# Motors_Sheet.net
KiCad netlist of a schematic drawn in Altium Designer
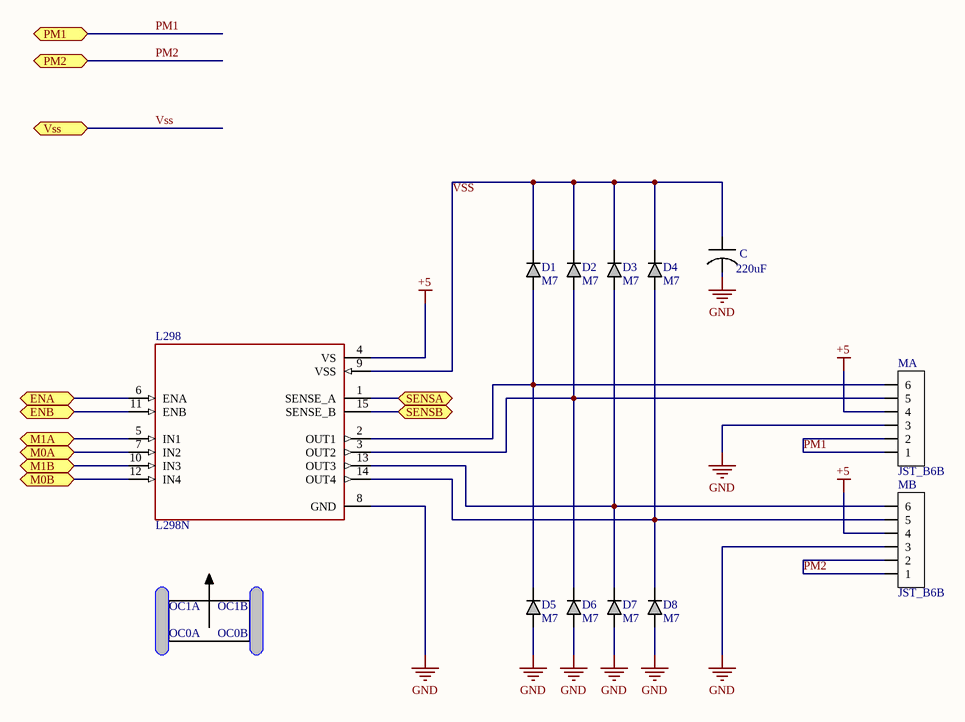
[diagram p0: Motors_Sheet.SchDoc]

(export (version "E")
  (design (tool "Eeschema 10.0.6"))
  (components
    (comp (ref "C")
      (value "220uF")
      (footprint "CAP_8115")
      (fields (field (name "Comment") "cap_elec8115"))
      (libsource (lib "cap_elec") (part "cap_elec8115"))
    )
    (comp (ref "D1") (value "M7") (footprint "1N4007") (libsource (lib "1N4007") (part "1N4007")))
    (comp (ref "D2") (value "M7") (footprint "1N4007") (libsource (lib "1N4007") (part "1N4007")))
    (comp (ref "D3") (value "M7") (footprint "1N4007") (libsource (lib "1N4007") (part "1N4007")))
    (comp (ref "D4") (value "M7") (footprint "1N4007") (libsource (lib "1N4007") (part "1N4007")))
    (comp (ref "D5") (value "M7") (footprint "1N4007") (libsource (lib "1N4007") (part "1N4007")))
    (comp (ref "D6") (value "M7") (footprint "1N4007") (libsource (lib "1N4007") (part "1N4007")))
    (comp (ref "D7") (value "M7") (footprint "1N4007") (libsource (lib "1N4007") (part "1N4007")))
    (comp (ref "D8") (value "M7") (footprint "1N4007") (libsource (lib "1N4007") (part "1N4007")))
    (comp (ref "L298") (value "L298N") (footprint "L298N") (libsource (lib "L298N") (part "L298N")))
    (comp (ref "MA") (value "JST_B6B") (footprint "JST_B6B") (libsource (lib "JST_B6B") (part "JST_B6B")))
    (comp (ref "MB") (value "JST_B6B") (footprint "JST_B6B") (libsource (lib "JST_B6B") (part "JST_B6B")))
  )
  (nets
    (net (code "1") (name "+5") (class "Default")
      (node (ref "L298") (pin "4") (pinfunction "VS_4") (pintype "power_in"))
      (node (ref "MA") (pin "4") (pinfunction "4_4") (pintype "passive"))
      (node (ref "MB") (pin "4") (pinfunction "4_4") (pintype "passive"))
    )
    (net (code "2") (name "/ENA") (class "Default")
      (node (ref "L298") (pin "6") (pinfunction "ENA_6") (pintype "input"))
    )
    (net (code "3") (name "/ENB") (class "Default")
      (node (ref "L298") (pin "11") (pinfunction "ENB_11") (pintype "input"))
    )
    (net (code "4") (name "/M0A") (class "Default")
      (node (ref "L298") (pin "7") (pinfunction "IN2_7") (pintype "input"))
    )
    (net (code "5") (name "/M0B") (class "Default")
      (node (ref "L298") (pin "12") (pinfunction "IN4_12") (pintype "input"))
    )
    (net (code "6") (name "/M1A") (class "Default")
      (node (ref "L298") (pin "5") (pinfunction "IN1_5") (pintype "input"))
    )
    (net (code "7") (name "/M1B") (class "Default")
      (node (ref "L298") (pin "10") (pinfunction "IN3_10") (pintype "input"))
    )
    (net (code "8") (name "/PM1") (class "Default")
      (node (ref "MA") (pin "1") (pinfunction "1_1") (pintype "passive"))
      (node (ref "MA") (pin "2") (pinfunction "2_2") (pintype "passive"))
    )
    (net (code "9") (name "/PM2") (class "Default")
      (node (ref "MB") (pin "1") (pinfunction "1_1") (pintype "passive"))
      (node (ref "MB") (pin "2") (pinfunction "2_2") (pintype "passive"))
    )
    (net (code "10") (name "/SENSA") (class "Default")
      (node (ref "L298") (pin "1") (pinfunction "SENSE_A_1") (pintype "passive"))
    )
    (net (code "11") (name "/SENSB") (class "Default")
      (node (ref "L298") (pin "15") (pinfunction "SENSE_B_15") (pintype "passive"))
    )
    (net (code "12") (name "/VSS") (class "Default")
      (node (ref "C") (pin "pos") (pinfunction "pos_pos") (pintype "passive"))
      (node (ref "D1") (pin "C") (pinfunction "C_C") (pintype "passive"))
      (node (ref "D2") (pin "C") (pinfunction "C_C") (pintype "passive"))
      (node (ref "D3") (pin "C") (pinfunction "C_C") (pintype "passive"))
      (node (ref "D4") (pin "C") (pinfunction "C_C") (pintype "passive"))
      (node (ref "L298") (pin "9") (pinfunction "VSS_9") (pintype "input"))
    )
    (net (code "14") (name "GND") (class "Default")
      (node (ref "C") (pin "neg") (pinfunction "neg_neg") (pintype "passive"))
      (node (ref "D5") (pin "A") (pinfunction "A_A") (pintype "passive"))
      (node (ref "D6") (pin "A") (pinfunction "A_A") (pintype "passive"))
      (node (ref "D7") (pin "A") (pinfunction "A_A") (pintype "passive"))
      (node (ref "D8") (pin "A") (pinfunction "A_A") (pintype "passive"))
      (node (ref "L298") (pin "8") (pinfunction "GND_8") (pintype "power_in"))
      (node (ref "MA") (pin "3") (pinfunction "3_3") (pintype "passive"))
      (node (ref "MB") (pin "3") (pinfunction "3_3") (pintype "passive"))
    )
    (net (code "15") (name "Net-(L298-OUT1)") (class "Default")
      (node (ref "D1") (pin "A") (pinfunction "A_A") (pintype "passive"))
      (node (ref "D5") (pin "C") (pinfunction "C_C") (pintype "passive"))
      (node (ref "L298") (pin "2") (pinfunction "OUT1_2") (pintype "output"))
      (node (ref "MA") (pin "6") (pinfunction "6_6") (pintype "passive"))
    )
    (net (code "16") (name "Net-(L298-OUT2)") (class "Default")
      (node (ref "D2") (pin "A") (pinfunction "A_A") (pintype "passive"))
      (node (ref "D6") (pin "C") (pinfunction "C_C") (pintype "passive"))
      (node (ref "L298") (pin "3") (pinfunction "OUT2_3") (pintype "output"))
      (node (ref "MA") (pin "5") (pinfunction "5_5") (pintype "passive"))
    )
    (net (code "17") (name "Net-(L298-OUT3)") (class "Default")
      (node (ref "D3") (pin "A") (pinfunction "A_A") (pintype "passive"))
      (node (ref "D7") (pin "C") (pinfunction "C_C") (pintype "passive"))
      (node (ref "L298") (pin "13") (pinfunction "OUT3_13") (pintype "output"))
      (node (ref "MB") (pin "6") (pinfunction "6_6") (pintype "passive"))
    )
    (net (code "18") (name "Net-(L298-OUT4)") (class "Default")
      (node (ref "D4") (pin "A") (pinfunction "A_A") (pintype "passive"))
      (node (ref "D8") (pin "C") (pinfunction "C_C") (pintype "passive"))
      (node (ref "L298") (pin "14") (pinfunction "OUT4_14") (pintype "output"))
      (node (ref "MB") (pin "5") (pinfunction "5_5") (pintype "passive"))
    )
  )
)
